# AtMEGA_IC.net
KiCad netlist of a schematic drawn in Altium Designer
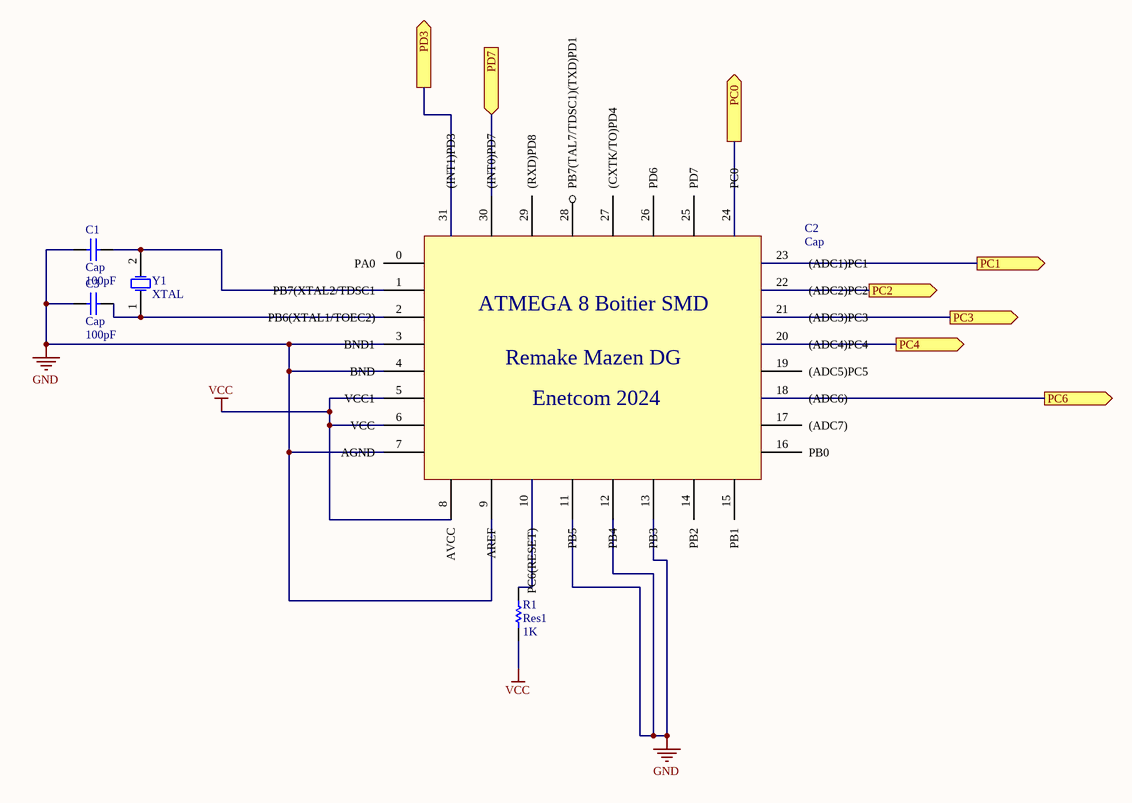
[diagram p0: AtMEGA IC.SchDoc]

(export (version "E")
  (design (tool "Eeschema 10.0.6"))
  (components
    (comp (ref "C1")
      (value "Cap")
      (footprint "RAD-0.3")
      (description "Capacitor")
      (fields (field (name "ALTIUM_VALUE") "100pF") (field (name "PUBLISHER") "Altium Limited"))
      (libsource (lib "Miscellaneous Devices") (part "Cap"))
    )
    (comp (ref "C2")
      (value "Cap")
      (footprint "Atmega_MAZENKOVIC")
      (description "Capacitor")
      (fields (field (name "PUBLISHER") "Altium Limited"))
      (libsource (lib "atmega8") (part "Component_1"))
    )
    (comp (ref "C3")
      (value "Cap")
      (footprint "RAD-0.3")
      (description "Capacitor")
      (fields (field (name "ALTIUM_VALUE") "100pF") (field (name "PUBLISHER") "Altium Limited"))
      (libsource (lib "Miscellaneous Devices") (part "Cap"))
    )
    (comp (ref "R1")
      (value "Res1")
      (footprint "AXIAL-0.3")
      (description "Resistor")
      (fields (field (name "ALTIUM_VALUE") "1K") (field (name "PUBLISHER") "Altium Limited"))
      (libsource (lib "Miscellaneous Devices") (part "Res1"))
    )
    (comp (ref "Y1")
      (value "XTAL")
      (footprint "R38")
      (description "Crystal Oscillator")
      (fields (field (name "PUBLISHER") "Altium Limited"))
      (libsource (lib "Miscellaneous Devices") (part "XTAL"))
    )
  )
  (nets
    (net (code "1") (name "/PC0") (class "Default")
      (node (ref "C2") (pin "24") (pinfunction "PC0_24") (pintype "passive"))
    )
    (net (code "2") (name "/PC1") (class "Default")
      (node (ref "C2") (pin "23") (pinfunction "(ADC1)PC1_23") (pintype "passive"))
    )
    (net (code "3") (name "/PC2") (class "Default")
      (node (ref "C2") (pin "22") (pinfunction "(ADC2)PC2_22") (pintype "passive"))
    )
    (net (code "4") (name "/PC3") (class "Default")
      (node (ref "C2") (pin "21") (pinfunction "(ADC3)PC3_21") (pintype "passive"))
    )
    (net (code "5") (name "/PC4") (class "Default")
      (node (ref "C2") (pin "20") (pinfunction "(ADC4)PC4_20") (pintype "passive"))
    )
    (net (code "6") (name "/PC6") (class "Default")
      (node (ref "C2") (pin "18") (pinfunction "(ADC6)_18") (pintype "passive"))
    )
    (net (code "7") (name "/PD3") (class "Default")
      (node (ref "C2") (pin "31") (pinfunction "(INT1)PD3_31") (pintype "passive"))
    )
    (net (code "9") (name "GND") (class "Default")
      (node (ref "C1") (pin "1") (pinfunction "1_1") (pintype "passive"))
      (node (ref "C3") (pin "1") (pinfunction "1_1") (pintype "passive"))
    )
    (net (code "10") (name "Net-(C2-PC6(RESET))") (class "Default")
      (node (ref "C2") (pin "10") (pinfunction "PC6(RESET)_10") (pintype "passive"))
      (node (ref "R1") (pin "2") (pinfunction "2_2") (pintype "passive"))
    )
    (net (code "11") (name "Net-(Y1-OSC1)") (class "Default")
      (node (ref "C3") (pin "2") (pinfunction "2_2") (pintype "passive"))
      (node (ref "Y1") (pin "1") (pinfunction "OSC1_1") (pintype "passive"))
    )
    (net (code "12") (name "Net-(Y1-OSC2)") (class "Default")
      (node (ref "C1") (pin "2") (pinfunction "2_2") (pintype "passive"))
      (node (ref "Y1") (pin "2") (pinfunction "OSC2_2") (pintype "passive"))
    )
    (net (code "13") (name "VCC") (class "Default")
      (node (ref "R1") (pin "1") (pinfunction "1_1") (pintype "passive"))
    )
    (net (code "14") (name "unconnected-(C2-(ADC5)PC5-Pad19)") (class "Default")
      (node (ref "C2") (pin "19") (pinfunction "(ADC5)PC5_19") (pintype "passive"))
    )
    (net (code "15") (name "unconnected-(C2-(ADC7)-Pad17)") (class "Default")
      (node (ref "C2") (pin "17") (pinfunction "(ADC7)_17") (pintype "passive"))
    )
    (net (code "16") (name "unconnected-(C2-(CXTK{slash}TO)PD4-Pad27)") (class "Default")
      (node (ref "C2") (pin "27") (pinfunction "(CXTK/TO)PD4_27") (pintype "passive"))
    )
    (net (code "17") (name "unconnected-(C2-(INT0)PD7-Pad30)") (class "Default")
      (node (ref "C2") (pin "30") (pinfunction "(INT0)PD7_30") (pintype "passive"))
    )
    (net (code "18") (name "unconnected-(C2-(RXD)PD8-Pad29)") (class "Default")
      (node (ref "C2") (pin "29") (pinfunction "(RXD)PD8_29") (pintype "passive"))
    )
    (net (code "19") (name "unconnected-(C2-AGND-Pad7)") (class "Default")
      (node (ref "C2") (pin "7") (pinfunction "AGND_7") (pintype "passive"))
    )
    (net (code "20") (name "unconnected-(C2-AREF-Pad9)") (class "Default")
      (node (ref "C2") (pin "9") (pinfunction "AREF_9") (pintype "passive"))
    )
    (net (code "21") (name "unconnected-(C2-AVCC-Pad8)") (class "Default")
      (node (ref "C2") (pin "8") (pinfunction "AVCC_8") (pintype "passive"))
    )
    (net (code "22") (name "unconnected-(C2-BND-Pad4)") (class "Default")
      (node (ref "C2") (pin "4") (pinfunction "BND_4") (pintype "passive"))
    )
    (net (code "23") (name "unconnected-(C2-BND1-Pad3)") (class "Default")
      (node (ref "C2") (pin "3") (pinfunction "BND1_3") (pintype "passive"))
    )
    (net (code "24") (name "unconnected-(C2-PA0-Pad0)") (class "Default")
      (node (ref "C2") (pin "0") (pinfunction "PA0_0") (pintype "passive"))
    )
    (net (code "25") (name "unconnected-(C2-PB0-Pad16)") (class "Default")
      (node (ref "C2") (pin "16") (pinfunction "PB0_16") (pintype "passive"))
    )
    (net (code "26") (name "unconnected-(C2-PB1-Pad15)") (class "Default")
      (node (ref "C2") (pin "15") (pinfunction "PB1_15") (pintype "passive"))
    )
    (net (code "27") (name "unconnected-(C2-PB2-Pad14)") (class "Default")
      (node (ref "C2") (pin "14") (pinfunction "PB2_14") (pintype "passive"))
    )
    (net (code "28") (name "unconnected-(C2-PB3-Pad13)") (class "Default")
      (node (ref "C2") (pin "13") (pinfunction "PB3_13") (pintype "passive"))
    )
    (net (code "29") (name "unconnected-(C2-PB4-Pad12)") (class "Default")
      (node (ref "C2") (pin "12") (pinfunction "PB4_12") (pintype "passive"))
    )
    (net (code "30") (name "unconnected-(C2-PB5-Pad11)") (class "Default")
      (node (ref "C2") (pin "11") (pinfunction "PB5_11") (pintype "passive"))
    )
    (net (code "31") (name "unconnected-(C2-PB6(XTAL1{slash}TOEC2)-Pad2)") (class "Default")
      (node (ref "C2") (pin "2") (pinfunction "PB6(XTAL1/TOEC2)_2") (pintype "passive"))
    )
    (net (code "32") (name "unconnected-(C2-PB7(TAL7{slash}TDSC1)(TXD)PD1-Pad28)") (class "Default")
      (node (ref "C2") (pin "28") (pinfunction "PB7(TAL7/TDSC1)(TXD)PD1_28") (pintype "passive"))
    )
    (net (code "33") (name "unconnected-(C2-PB7(XTAL2{slash}TDSC1-Pad1)") (class "Default")
      (node (ref "C2") (pin "1") (pinfunction "PB7(XTAL2/TDSC1_1") (pintype "passive"))
    )
    (net (code "34") (name "unconnected-(C2-PD6-Pad26)") (class "Default")
      (node (ref "C2") (pin "26") (pinfunction "PD6_26") (pintype "passive"))
    )
    (net (code "35") (name "unconnected-(C2-PD7-Pad25)") (class "Default")
      (node (ref "C2") (pin "25") (pinfunction "PD7_25") (pintype "passive"))
    )
    (net (code "36") (name "unconnected-(C2-VCC-Pad6)") (class "Default")
      (node (ref "C2") (pin "6") (pinfunction "VCC_6") (pintype "passive"))
    )
    (net (code "37") (name "unconnected-(C2-VCC1-Pad5)") (class "Default")
      (node (ref "C2") (pin "5") (pinfunction "VCC1_5") (pintype "passive"))
    )
  )
)
